# EmgAcq.net
KiCad netlist of a schematic drawn in Altium Designer
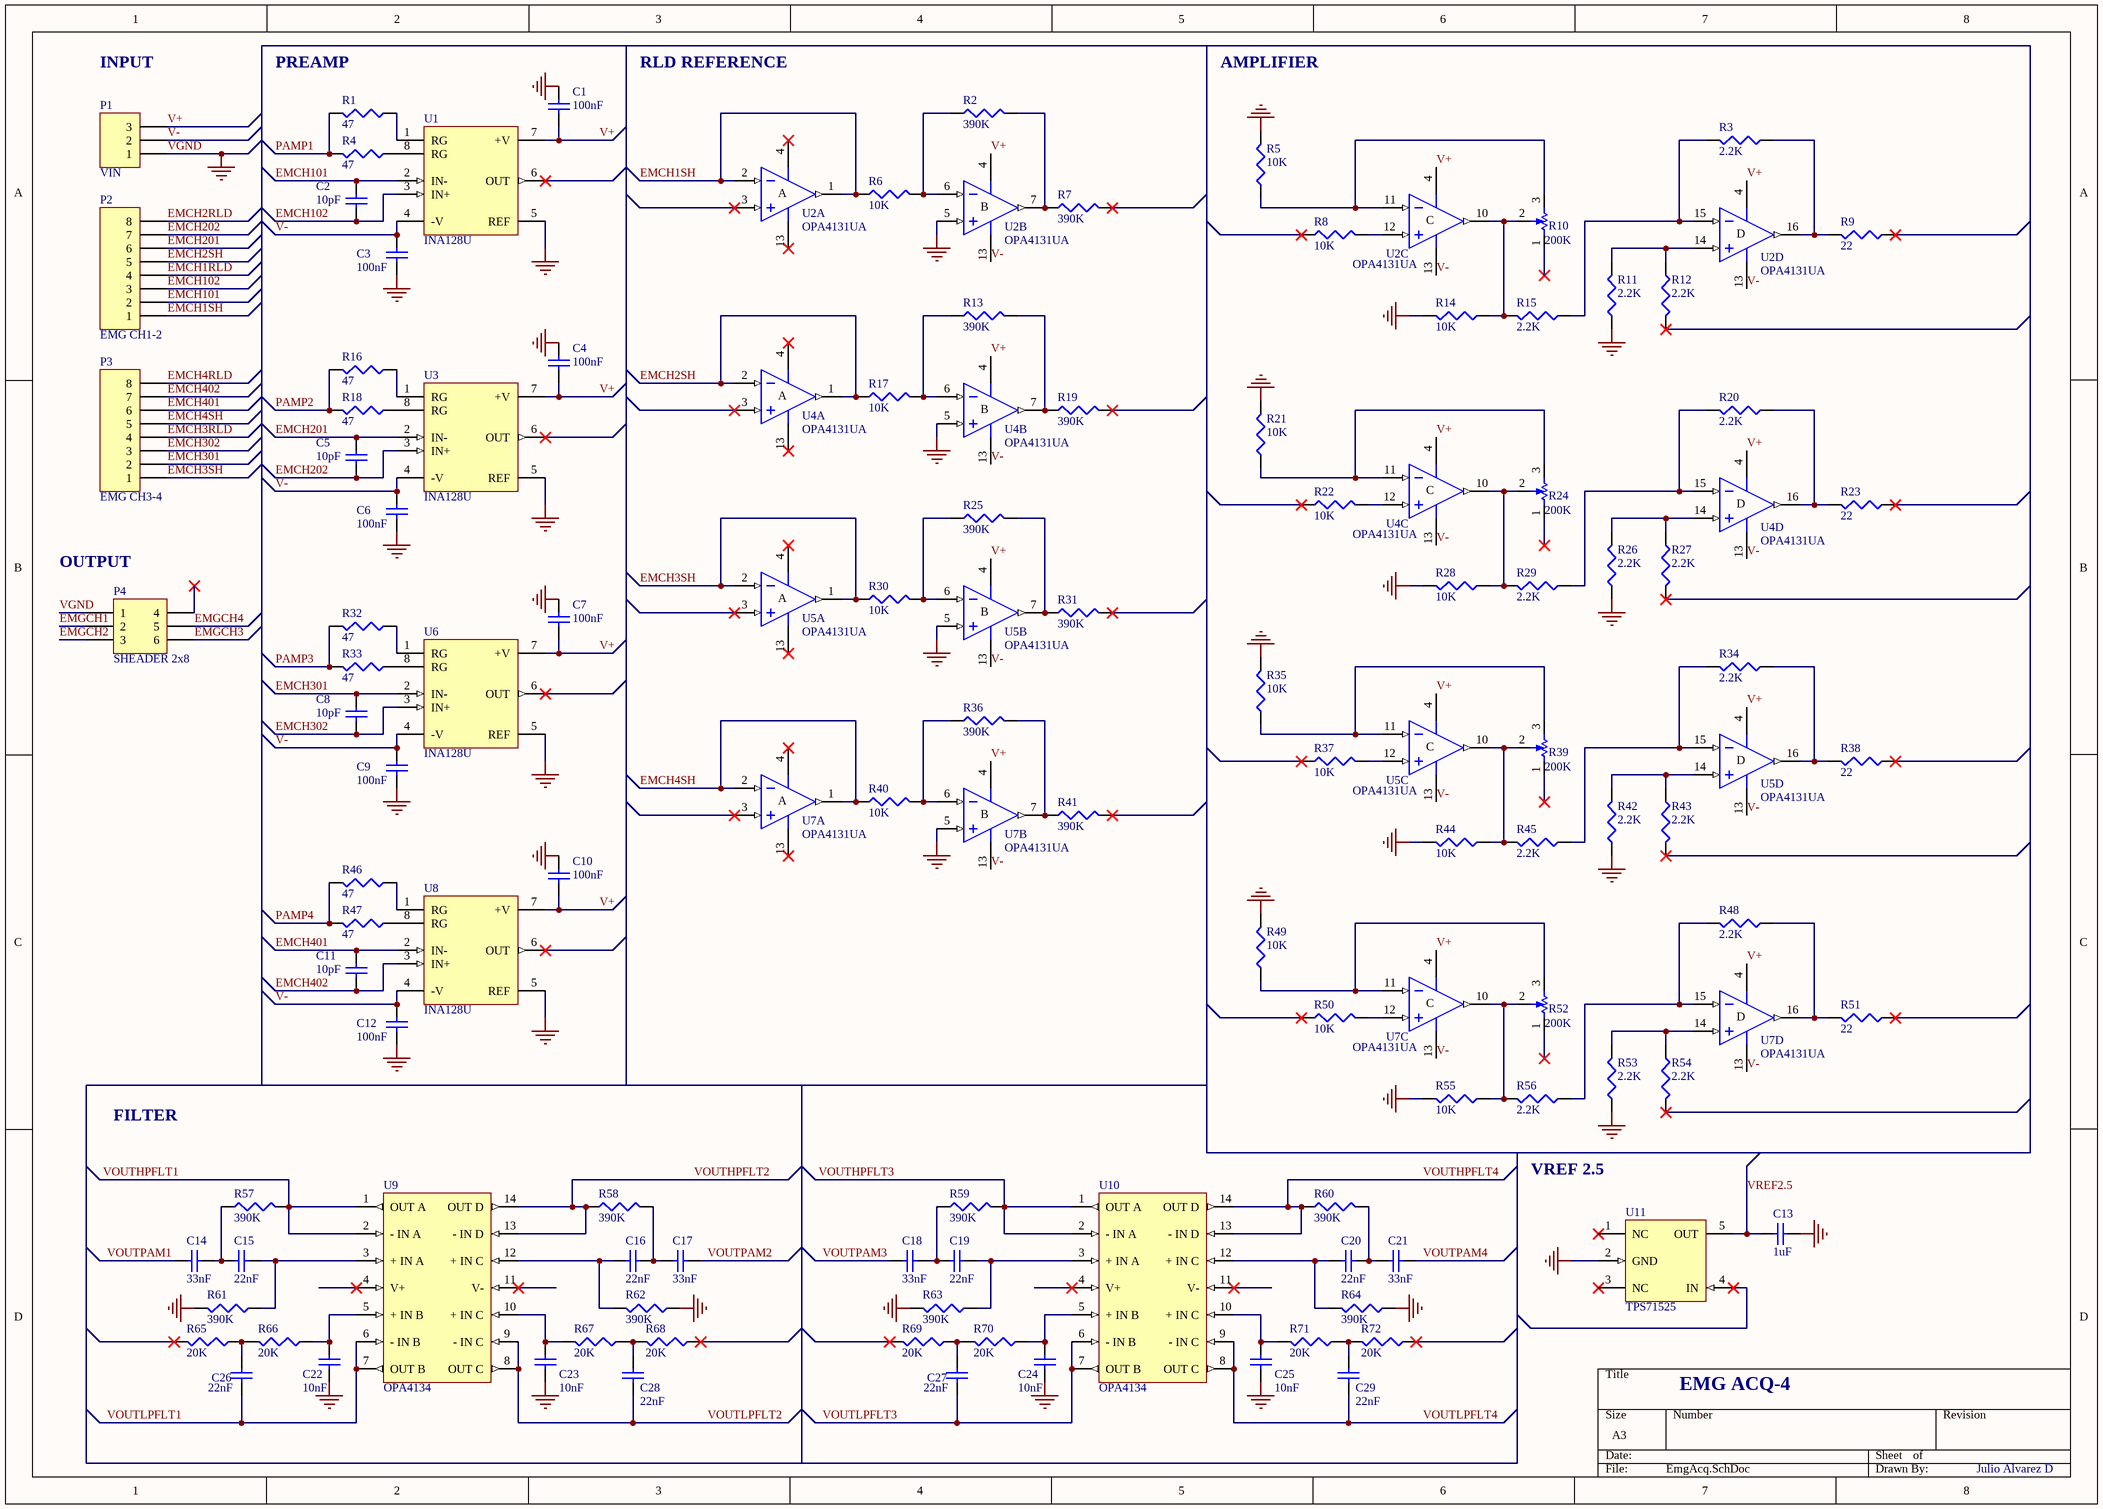
[diagram p0: EmgAcq.SchDoc]

(export (version "E")
  (design (tool "Eeschema 10.0.6"))
  (components
    (comp (ref "C1")
      (value "100nF")
      (footprint "C1206")
      (description "Capacitor (Semiconductor SIM Model)")
      (fields (field (name "Comment") "Cap Semi") (field (name "PUBLISHER") "Altium Limited"))
      (libsource (lib "Miscellaneous Devices") (part "Cap Semi"))
    )
    (comp (ref "C2")
      (value "10pF")
      (footprint "C1206")
      (description "Capacitor (Semiconductor SIM Model)")
      (fields (field (name "Comment") "Cap Semi") (field (name "PUBLISHER") "Altium Limited"))
      (libsource (lib "Miscellaneous Devices") (part "Cap Semi"))
    )
    (comp (ref "C3")
      (value "100nF")
      (footprint "C1206")
      (description "Capacitor (Semiconductor SIM Model)")
      (fields (field (name "Comment") "Cap Semi") (field (name "PUBLISHER") "Altium Limited"))
      (libsource (lib "Miscellaneous Devices") (part "Cap Semi"))
    )
    (comp (ref "C4")
      (value "100nF")
      (footprint "C1206")
      (description "Capacitor (Semiconductor SIM Model)")
      (fields (field (name "Comment") "Cap Semi") (field (name "PUBLISHER") "Altium Limited"))
      (libsource (lib "Miscellaneous Devices") (part "Cap Semi"))
    )
    (comp (ref "C5")
      (value "10pF")
      (footprint "C1206")
      (description "Capacitor (Semiconductor SIM Model)")
      (fields (field (name "Comment") "Cap Semi") (field (name "PUBLISHER") "Altium Limited"))
      (libsource (lib "Miscellaneous Devices") (part "Cap Semi"))
    )
    (comp (ref "C6")
      (value "100nF")
      (footprint "C1206")
      (description "Capacitor (Semiconductor SIM Model)")
      (fields (field (name "Comment") "Cap Semi") (field (name "PUBLISHER") "Altium Limited"))
      (libsource (lib "Miscellaneous Devices") (part "Cap Semi"))
    )
    (comp (ref "C7")
      (value "100nF")
      (footprint "C1206")
      (description "Capacitor (Semiconductor SIM Model)")
      (fields (field (name "Comment") "Cap Semi") (field (name "PUBLISHER") "Altium Limited"))
      (libsource (lib "Miscellaneous Devices") (part "Cap Semi"))
    )
    (comp (ref "C8")
      (value "10pF")
      (footprint "C1206")
      (description "Capacitor (Semiconductor SIM Model)")
      (fields (field (name "Comment") "Cap Semi") (field (name "PUBLISHER") "Altium Limited"))
      (libsource (lib "Miscellaneous Devices") (part "Cap Semi"))
    )
    (comp (ref "C9")
      (value "100nF")
      (footprint "C1206")
      (description "Capacitor (Semiconductor SIM Model)")
      (fields (field (name "Comment") "Cap Semi") (field (name "PUBLISHER") "Altium Limited"))
      (libsource (lib "Miscellaneous Devices") (part "Cap Semi"))
    )
    (comp (ref "C10")
      (value "100nF")
      (footprint "C1206")
      (description "Capacitor (Semiconductor SIM Model)")
      (fields (field (name "Comment") "Cap Semi") (field (name "PUBLISHER") "Altium Limited"))
      (libsource (lib "Miscellaneous Devices") (part "Cap Semi"))
    )
    (comp (ref "C11")
      (value "10pF")
      (footprint "C1206")
      (description "Capacitor (Semiconductor SIM Model)")
      (fields (field (name "Comment") "Cap Semi") (field (name "PUBLISHER") "Altium Limited"))
      (libsource (lib "Miscellaneous Devices") (part "Cap Semi"))
    )
    (comp (ref "C12")
      (value "100nF")
      (footprint "C1206")
      (description "Capacitor (Semiconductor SIM Model)")
      (fields (field (name "Comment") "Cap Semi") (field (name "PUBLISHER") "Altium Limited"))
      (libsource (lib "Miscellaneous Devices") (part "Cap Semi"))
    )
    (comp (ref "C13")
      (value "1uF")
      (footprint "CAPC2012M")
      (description "Capacitor (Semiconductor SIM Model)")
      (fields (field (name "Comment") "Cap Semi") (field (name "PUBLISHER") "Altium Limited"))
      (libsource (lib "Miscellaneous Devices") (part "Cap Semi"))
    )
    (comp (ref "C14")
      (value "33nF")
      (footprint "C1206")
      (description "Capacitor (Semiconductor SIM Model)")
      (fields (field (name "Comment") "Cap Semi") (field (name "PUBLISHER") "Altium Limited"))
      (libsource (lib "Miscellaneous Devices") (part "Cap Semi"))
    )
    (comp (ref "C15")
      (value "22nF")
      (footprint "1608[0603]")
      (description "Capacitor (Semiconductor SIM Model)")
      (fields (field (name "Comment") "Cap Semi") (field (name "PUBLISHER") "Altium Limited"))
      (libsource (lib "Miscellaneous Devices") (part "Cap Semi"))
    )
    (comp (ref "C16")
      (value "22nF")
      (footprint "1608[0603]")
      (description "Capacitor (Semiconductor SIM Model)")
      (fields (field (name "Comment") "Cap Semi") (field (name "PUBLISHER") "Altium Limited"))
      (libsource (lib "Miscellaneous Devices") (part "Cap Semi"))
    )
    (comp (ref "C17")
      (value "33nF")
      (footprint "C1206")
      (description "Capacitor (Semiconductor SIM Model)")
      (fields (field (name "Comment") "Cap Semi") (field (name "PUBLISHER") "Altium Limited"))
      (libsource (lib "Miscellaneous Devices") (part "Cap Semi"))
    )
    (comp (ref "C18")
      (value "33nF")
      (footprint "C1206")
      (description "Capacitor (Semiconductor SIM Model)")
      (fields (field (name "Comment") "Cap Semi") (field (name "PUBLISHER") "Altium Limited"))
      (libsource (lib "Miscellaneous Devices") (part "Cap Semi"))
    )
    (comp (ref "C19")
      (value "22nF")
      (footprint "1608[0603]")
      (description "Capacitor (Semiconductor SIM Model)")
      (fields (field (name "Comment") "Cap Semi") (field (name "PUBLISHER") "Altium Limited"))
      (libsource (lib "Miscellaneous Devices") (part "Cap Semi"))
    )
    (comp (ref "C20")
      (value "22nF")
      (footprint "1608[0603]")
      (description "Capacitor (Semiconductor SIM Model)")
      (fields (field (name "Comment") "Cap Semi") (field (name "PUBLISHER") "Altium Limited"))
      (libsource (lib "Miscellaneous Devices") (part "Cap Semi"))
    )
    (comp (ref "C21")
      (value "33nF")
      (footprint "C1206")
      (description "Capacitor (Semiconductor SIM Model)")
      (fields (field (name "Comment") "Cap Semi") (field (name "PUBLISHER") "Altium Limited"))
      (libsource (lib "Miscellaneous Devices") (part "Cap Semi"))
    )
    (comp (ref "C22")
      (value "10nF")
      (footprint "C1206")
      (description "Capacitor (Semiconductor SIM Model)")
      (fields (field (name "Comment") "Cap Semi") (field (name "PUBLISHER") "Altium Limited"))
      (libsource (lib "Miscellaneous Devices") (part "Cap Semi"))
    )
    (comp (ref "C23")
      (value "10nF")
      (footprint "C1206")
      (description "Capacitor (Semiconductor SIM Model)")
      (fields (field (name "Comment") "Cap Semi") (field (name "PUBLISHER") "Altium Limited"))
      (libsource (lib "Miscellaneous Devices") (part "Cap Semi"))
    )
    (comp (ref "C24")
      (value "10nF")
      (footprint "C1206")
      (description "Capacitor (Semiconductor SIM Model)")
      (fields (field (name "Comment") "Cap Semi") (field (name "PUBLISHER") "Altium Limited"))
      (libsource (lib "Miscellaneous Devices") (part "Cap Semi"))
    )
    (comp (ref "C25")
      (value "10nF")
      (footprint "C1206")
      (description "Capacitor (Semiconductor SIM Model)")
      (fields (field (name "Comment") "Cap Semi") (field (name "PUBLISHER") "Altium Limited"))
      (libsource (lib "Miscellaneous Devices") (part "Cap Semi"))
    )
    (comp (ref "C26")
      (value "22nF")
      (footprint "1608[0603]")
      (description "Capacitor (Semiconductor SIM Model)")
      (fields (field (name "Comment") "Cap Semi") (field (name "PUBLISHER") "Altium Limited"))
      (libsource (lib "Miscellaneous Devices") (part "Cap Semi"))
    )
    (comp (ref "C27")
      (value "22nF")
      (footprint "1608[0603]")
      (description "Capacitor (Semiconductor SIM Model)")
      (fields (field (name "Comment") "Cap Semi") (field (name "PUBLISHER") "Altium Limited"))
      (libsource (lib "Miscellaneous Devices") (part "Cap Semi"))
    )
    (comp (ref "C28")
      (value "22nF")
      (footprint "1608[0603]")
      (description "Capacitor (Semiconductor SIM Model)")
      (fields (field (name "Comment") "Cap Semi") (field (name "PUBLISHER") "Altium Limited"))
      (libsource (lib "Miscellaneous Devices") (part "Cap Semi"))
    )
    (comp (ref "C29")
      (value "22nF")
      (footprint "1608[0603]")
      (description "Capacitor (Semiconductor SIM Model)")
      (fields (field (name "Comment") "Cap Semi") (field (name "PUBLISHER") "Altium Limited"))
      (libsource (lib "Miscellaneous Devices") (part "Cap Semi"))
    )
    (comp (ref "P1")
      (value "VIN")
      (footprint "AZUL5-3")
      (description "Header, 3-Pin")
      (fields (field (name "PUBLISHER") "Altium Limited"))
      (libsource (lib "Miscellaneous Connectors") (part "Header 3"))
    )
    (comp (ref "P2")
      (value "EMG CH1-2")
      (footprint "AZUL5-8")
      (description "Header, 8-Pin")
      (fields (field (name "PUBLISHER") "Altium Limited"))
      (libsource (lib "Miscellaneous Connectors") (part "Header 8"))
    )
    (comp (ref "P3")
      (value "EMG CH3-4")
      (footprint "AZUL5-8")
      (description "Header, 8-Pin")
      (fields (field (name "PUBLISHER") "Altium Limited"))
      (libsource (lib "Miscellaneous Connectors") (part "Header 8"))
    )
    (comp (ref "P4")
      (value "SHEADER 2x8")
      (footprint "SHBH 2x3")
      (description "Shrouded Box Header: 2x8-Pin, 0.100\" (2.54 mm) Male")
      (libsource (lib "LitoLibrary") (part "SB Header 2x3"))
    )
    (comp (ref "R1")
      (value "47")
      (footprint "RESC3225M")
      (description "Resistor")
      (fields (field (name "Comment") "Res3") (field (name "PUBLISHER") "Altium Limited"))
      (libsource (lib "Miscellaneous Devices") (part "Res3"))
    )
    (comp (ref "R2")
      (value "390K")
      (footprint "RESC3225M")
      (description "Resistor")
      (fields (field (name "Comment") "Res3") (field (name "PUBLISHER") "Altium Limited"))
      (libsource (lib "Miscellaneous Devices") (part "Res3"))
    )
    (comp (ref "R3")
      (value "2.2K")
      (footprint "RESC3225M")
      (description "Resistor")
      (fields (field (name "Comment") "Res3") (field (name "PUBLISHER") "Altium Limited"))
      (libsource (lib "Miscellaneous Devices") (part "Res3"))
    )
    (comp (ref "R4")
      (value "47")
      (footprint "RESC3225M")
      (description "Resistor")
      (fields (field (name "Comment") "Res3") (field (name "PUBLISHER") "Altium Limited"))
      (libsource (lib "Miscellaneous Devices") (part "Res3"))
    )
    (comp (ref "R5")
      (value "10K")
      (footprint "RESC3225M")
      (description "Resistor")
      (fields (field (name "Comment") "Res3") (field (name "PUBLISHER") "Altium Limited"))
      (libsource (lib "Miscellaneous Devices") (part "Res3"))
    )
    (comp (ref "R6")
      (value "10K")
      (footprint "RESC3225M")
      (description "Resistor")
      (fields (field (name "Comment") "Res3") (field (name "PUBLISHER") "Altium Limited"))
      (libsource (lib "Miscellaneous Devices") (part "Res3"))
    )
    (comp (ref "R7")
      (value "390K")
      (footprint "RESC3225M")
      (description "Resistor")
      (fields (field (name "Comment") "Res3") (field (name "PUBLISHER") "Altium Limited"))
      (libsource (lib "Miscellaneous Devices") (part "Res3"))
    )
    (comp (ref "R8")
      (value "10K")
      (footprint "RESC3225M")
      (description "Resistor")
      (fields (field (name "Comment") "Res3") (field (name "PUBLISHER") "Altium Limited"))
      (libsource (lib "Miscellaneous Devices") (part "Res3"))
    )
    (comp (ref "R9")
      (value "22")
      (footprint "RESC3225M")
      (description "Resistor")
      (fields (field (name "Comment") "Res3") (field (name "PUBLISHER") "Altium Limited"))
      (libsource (lib "Miscellaneous Devices") (part "Res3"))
    )
    (comp (ref "R10")
      (value "POT3361")
      (footprint "3361P")
      (fields (field (name "ALTIUM_UNNAMED_1") "200K"))
      (libsource (lib "LitoLibrary") (part "POT3361"))
    )
    (comp (ref "R11")
      (value "2.2K")
      (footprint "RESC3225M")
      (description "Resistor")
      (fields (field (name "Comment") "Res3") (field (name "PUBLISHER") "Altium Limited"))
      (libsource (lib "Miscellaneous Devices") (part "Res3"))
    )
    (comp (ref "R12")
      (value "2.2K")
      (footprint "RESC3225M")
      (description "Resistor")
      (fields (field (name "Comment") "Res3") (field (name "PUBLISHER") "Altium Limited"))
      (libsource (lib "Miscellaneous Devices") (part "Res3"))
    )
    (comp (ref "R13")
      (value "390K")
      (footprint "RESC3225M")
      (description "Resistor")
      (fields (field (name "Comment") "Res3") (field (name "PUBLISHER") "Altium Limited"))
      (libsource (lib "Miscellaneous Devices") (part "Res3"))
    )
    (comp (ref "R14")
      (value "10K")
      (footprint "RESC3225M")
      (description "Resistor")
      (fields (field (name "Comment") "Res3") (field (name "PUBLISHER") "Altium Limited"))
      (libsource (lib "Miscellaneous Devices") (part "Res3"))
    )
    (comp (ref "R15")
      (value "2.2K")
      (footprint "RESC3225M")
      (description "Resistor")
      (fields (field (name "Comment") "Res3") (field (name "PUBLISHER") "Altium Limited"))
      (libsource (lib "Miscellaneous Devices") (part "Res3"))
    )
    (comp (ref "R16")
      (value "47")
      (footprint "RESC3225M")
      (description "Resistor")
      (fields (field (name "Comment") "Res3") (field (name "PUBLISHER") "Altium Limited"))
      (libsource (lib "Miscellaneous Devices") (part "Res3"))
    )
    (comp (ref "R17")
      (value "10K")
      (footprint "RESC3225M")
      (description "Resistor")
      (fields (field (name "Comment") "Res3") (field (name "PUBLISHER") "Altium Limited"))
      (libsource (lib "Miscellaneous Devices") (part "Res3"))
    )
    (comp (ref "R18")
      (value "47")
      (footprint "RESC3225M")
      (description "Resistor")
      (fields (field (name "Comment") "Res3") (field (name "PUBLISHER") "Altium Limited"))
      (libsource (lib "Miscellaneous Devices") (part "Res3"))
    )
    (comp (ref "R19")
      (value "390K")
      (footprint "RESC3225M")
      (description "Resistor")
      (fields (field (name "Comment") "Res3") (field (name "PUBLISHER") "Altium Limited"))
      (libsource (lib "Miscellaneous Devices") (part "Res3"))
    )
    (comp (ref "R20")
      (value "2.2K")
      (footprint "RESC3225M")
      (description "Resistor")
      (fields (field (name "Comment") "Res3") (field (name "PUBLISHER") "Altium Limited"))
      (libsource (lib "Miscellaneous Devices") (part "Res3"))
    )
    (comp (ref "R21")
      (value "10K")
      (footprint "RESC3225M")
      (description "Resistor")
      (fields (field (name "Comment") "Res3") (field (name "PUBLISHER") "Altium Limited"))
      (libsource (lib "Miscellaneous Devices") (part "Res3"))
    )
    (comp (ref "R22")
      (value "10K")
      (footprint "RESC3225M")
      (description "Resistor")
      (fields (field (name "Comment") "Res3") (field (name "PUBLISHER") "Altium Limited"))
      (libsource (lib "Miscellaneous Devices") (part "Res3"))
    )
    (comp (ref "R23")
      (value "22")
      (footprint "RESC3225M")
      (description "Resistor")
      (fields (field (name "Comment") "Res3") (field (name "PUBLISHER") "Altium Limited"))
      (libsource (lib "Miscellaneous Devices") (part "Res3"))
    )
    (comp (ref "R24")
      (value "POT3361")
      (footprint "3361P")
      (fields (field (name "ALTIUM_UNNAMED_1") "200K"))
      (libsource (lib "LitoLibrary") (part "POT3361"))
    )
    (comp (ref "R25")
      (value "390K")
      (footprint "RESC3225M")
      (description "Resistor")
      (fields (field (name "Comment") "Res3") (field (name "PUBLISHER") "Altium Limited"))
      (libsource (lib "Miscellaneous Devices") (part "Res3"))
    )
    (comp (ref "R26")
      (value "2.2K")
      (footprint "RESC3225M")
      (description "Resistor")
      (fields (field (name "Comment") "Res3") (field (name "PUBLISHER") "Altium Limited"))
      (libsource (lib "Miscellaneous Devices") (part "Res3"))
    )
    (comp (ref "R27")
      (value "2.2K")
      (footprint "RESC3225M")
      (description "Resistor")
      (fields (field (name "Comment") "Res3") (field (name "PUBLISHER") "Altium Limited"))
      (libsource (lib "Miscellaneous Devices") (part "Res3"))
    )
    (comp (ref "R28")
      (value "10K")
      (footprint "RESC3225M")
      (description "Resistor")
      (fields (field (name "Comment") "Res3") (field (name "PUBLISHER") "Altium Limited"))
      (libsource (lib "Miscellaneous Devices") (part "Res3"))
    )
    (comp (ref "R29")
      (value "2.2K")
      (footprint "RESC3225M")
      (description "Resistor")
      (fields (field (name "Comment") "Res3") (field (name "PUBLISHER") "Altium Limited"))
      (libsource (lib "Miscellaneous Devices") (part "Res3"))
    )
    (comp (ref "R30")
      (value "10K")
      (footprint "RESC3225M")
      (description "Resistor")
      (fields (field (name "Comment") "Res3") (field (name "PUBLISHER") "Altium Limited"))
      (libsource (lib "Miscellaneous Devices") (part "Res3"))
    )
    (comp (ref "R31")
      (value "390K")
      (footprint "RESC3225M")
      (description "Resistor")
      (fields (field (name "Comment") "Res3") (field (name "PUBLISHER") "Altium Limited"))
      (libsource (lib "Miscellaneous Devices") (part "Res3"))
    )
    (comp (ref "R32")
      (value "47")
      (footprint "RESC3225M")
      (description "Resistor")
      (fields (field (name "Comment") "Res3") (field (name "PUBLISHER") "Altium Limited"))
      (libsource (lib "Miscellaneous Devices") (part "Res3"))
    )
    (comp (ref "R33")
      (value "47")
      (footprint "RESC3225M")
      (description "Resistor")
      (fields (field (name "Comment") "Res3") (field (name "PUBLISHER") "Altium Limited"))
      (libsource (lib "Miscellaneous Devices") (part "Res3"))
    )
    (comp (ref "R34")
      (value "2.2K")
      (footprint "RESC3225M")
      (description "Resistor")
      (fields (field (name "Comment") "Res3") (field (name "PUBLISHER") "Altium Limited"))
      (libsource (lib "Miscellaneous Devices") (part "Res3"))
    )
    (comp (ref "R35")
      (value "10K")
      (footprint "RESC3225M")
      (description "Resistor")
      (fields (field (name "Comment") "Res3") (field (name "PUBLISHER") "Altium Limited"))
      (libsource (lib "Miscellaneous Devices") (part "Res3"))
    )
    (comp (ref "R36")
      (value "390K")
      (footprint "RESC3225M")
      (description "Resistor")
      (fields (field (name "Comment") "Res3") (field (name "PUBLISHER") "Altium Limited"))
      (libsource (lib "Miscellaneous Devices") (part "Res3"))
    )
    (comp (ref "R37")
      (value "10K")
      (footprint "RESC3225M")
      (description "Resistor")
      (fields (field (name "Comment") "Res3") (field (name "PUBLISHER") "Altium Limited"))
      (libsource (lib "Miscellaneous Devices") (part "Res3"))
    )
    (comp (ref "R38")
      (value "22")
      (footprint "RESC3225M")
      (description "Resistor")
      (fields (field (name "Comment") "Res3") (field (name "PUBLISHER") "Altium Limited"))
      (libsource (lib "Miscellaneous Devices") (part "Res3"))
    )
    (comp (ref "R39")
      (value "POT3361")
      (footprint "3361P")
      (fields (field (name "ALTIUM_UNNAMED_1") "200K"))
      (libsource (lib "LitoLibrary") (part "POT3361"))
    )
    (comp (ref "R40")
      (value "10K")
      (footprint "RESC3225M")
      (description "Resistor")
      (fields (field (name "Comment") "Res3") (field (name "PUBLISHER") "Altium Limited"))
      (libsource (lib "Miscellaneous Devices") (part "Res3"))
    )
    (comp (ref "R41")
      (value "390K")
      (footprint "RESC3225M")
      (description "Resistor")
      (fields (field (name "Comment") "Res3") (field (name "PUBLISHER") "Altium Limited"))
      (libsource (lib "Miscellaneous Devices") (part "Res3"))
    )
    (comp (ref "R42")
      (value "2.2K")
      (footprint "RESC3225M")
      (description "Resistor")
      (fields (field (name "Comment") "Res3") (field (name "PUBLISHER") "Altium Limited"))
      (libsource (lib "Miscellaneous Devices") (part "Res3"))
    )
    (comp (ref "R43")
      (value "2.2K")
      (footprint "RESC3225M")
      (description "Resistor")
      (fields (field (name "Comment") "Res3") (field (name "PUBLISHER") "Altium Limited"))
      (libsource (lib "Miscellaneous Devices") (part "Res3"))
    )
    (comp (ref "R44")
      (value "10K")
      (footprint "RESC3225M")
      (description "Resistor")
      (fields (field (name "Comment") "Res3") (field (name "PUBLISHER") "Altium Limited"))
      (libsource (lib "Miscellaneous Devices") (part "Res3"))
    )
    (comp (ref "R45")
      (value "2.2K")
      (footprint "RESC3225M")
      (description "Resistor")
      (fields (field (name "Comment") "Res3") (field (name "PUBLISHER") "Altium Limited"))
      (libsource (lib "Miscellaneous Devices") (part "Res3"))
    )
    (comp (ref "R46")
      (value "47")
      (footprint "RESC3225M")
      (description "Resistor")
      (fields (field (name "Comment") "Res3") (field (name "PUBLISHER") "Altium Limited"))
      (libsource (lib "Miscellaneous Devices") (part "Res3"))
    )
    (comp (ref "R47")
      (value "47")
      (footprint "RESC3225M")
      (description "Resistor")
      (fields (field (name "Comment") "Res3") (field (name "PUBLISHER") "Altium Limited"))
      (libsource (lib "Miscellaneous Devices") (part "Res3"))
    )
    (comp (ref "R48")
      (value "2.2K")
      (footprint "RESC3225M")
      (description "Resistor")
      (fields (field (name "Comment") "Res3") (field (name "PUBLISHER") "Altium Limited"))
      (libsource (lib "Miscellaneous Devices") (part "Res3"))
    )
    (comp (ref "R49")
      (value "10K")
      (footprint "RESC3225M")
      (description "Resistor")
      (fields (field (name "Comment") "Res3") (field (name "PUBLISHER") "Altium Limited"))
      (libsource (lib "Miscellaneous Devices") (part "Res3"))
    )
    (comp (ref "R50")
      (value "10K")
      (footprint "RESC3225M")
      (description "Resistor")
      (fields (field (name "Comment") "Res3") (field (name "PUBLISHER") "Altium Limited"))
      (libsource (lib "Miscellaneous Devices") (part "Res3"))
    )
    (comp (ref "R51")
      (value "22")
      (footprint "RESC3225M")
      (description "Resistor")
      (fields (field (name "Comment") "Res3") (field (name "PUBLISHER") "Altium Limited"))
      (libsource (lib "Miscellaneous Devices") (part "Res3"))
    )
    (comp (ref "R52")
      (value "POT3361")
      (footprint "3361P")
      (fields (field (name "ALTIUM_UNNAMED_1") "200K"))
      (libsource (lib "LitoLibrary") (part "POT3361"))
    )
    (comp (ref "R53")
      (value "2.2K")
      (footprint "RESC3225M")
      (description "Resistor")
      (fields (field (name "Comment") "Res3") (field (name "PUBLISHER") "Altium Limited"))
      (libsource (lib "Miscellaneous Devices") (part "Res3"))
    )
    (comp (ref "R54")
      (value "2.2K")
      (footprint "RESC3225M")
      (description "Resistor")
      (fields (field (name "Comment") "Res3") (field (name "PUBLISHER") "Altium Limited"))
      (libsource (lib "Miscellaneous Devices") (part "Res3"))
    )
    (comp (ref "R55")
      (value "10K")
      (footprint "RESC3225M")
      (description "Resistor")
      (fields (field (name "Comment") "Res3") (field (name "PUBLISHER") "Altium Limited"))
      (libsource (lib "Miscellaneous Devices") (part "Res3"))
    )
    (comp (ref "R56")
      (value "2.2K")
      (footprint "RESC3225M")
      (description "Resistor")
      (fields (field (name "Comment") "Res3") (field (name "PUBLISHER") "Altium Limited"))
      (libsource (lib "Miscellaneous Devices") (part "Res3"))
    )
    (comp (ref "R57")
      (value "390K")
      (footprint "RESC3225M")
      (description "Resistor")
      (fields (field (name "Comment") "Res3") (field (name "PUBLISHER") "Altium Limited"))
      (libsource (lib "Miscellaneous Devices") (part "Res3"))
    )
    (comp (ref "R58")
      (value "390K")
      (footprint "RESC3225M")
      (description "Resistor")
      (fields (field (name "Comment") "Res3") (field (name "PUBLISHER") "Altium Limited"))
      (libsource (lib "Miscellaneous Devices") (part "Res3"))
    )
    (comp (ref "R59")
      (value "390K")
      (footprint "RESC3225M")
      (description "Resistor")
      (fields (field (name "Comment") "Res3") (field (name "PUBLISHER") "Altium Limited"))
      (libsource (lib "Miscellaneous Devices") (part "Res3"))
    )
    (comp (ref "R60")
      (value "390K")
      (footprint "RESC3225M")
      (description "Resistor")
      (fields (field (name "Comment") "Res3") (field (name "PUBLISHER") "Altium Limited"))
      (libsource (lib "Miscellaneous Devices") (part "Res3"))
    )
    (comp (ref "R61")
      (value "390K")
      (footprint "RESC3225M")
      (description "Resistor")
      (fields (field (name "Comment") "Res3") (field (name "PUBLISHER") "Altium Limited"))
      (libsource (lib "Miscellaneous Devices") (part "Res3"))
    )
    (comp (ref "R62")
      (value "390K")
      (footprint "RESC3225M")
      (description "Resistor")
      (fields (field (name "Comment") "Res3") (field (name "PUBLISHER") "Altium Limited"))
      (libsource (lib "Miscellaneous Devices") (part "Res3"))
    )
    (comp (ref "R63")
      (value "390K")
      (footprint "RESC3225M")
      (description "Resistor")
      (fields (field (name "Comment") "Res3") (field (name "PUBLISHER") "Altium Limited"))
      (libsource (lib "Miscellaneous Devices") (part "Res3"))
    )
    (comp (ref "R64")
      (value "390K")
      (footprint "RESC3225M")
      (description "Resistor")
      (fields (field (name "Comment") "Res3") (field (name "PUBLISHER") "Altium Limited"))
      (libsource (lib "Miscellaneous Devices") (part "Res3"))
    )
    (comp (ref "R65")
      (value "20K")
      (footprint "RESC3225M")
      (description "Resistor")
      (fields (field (name "Comment") "Res3") (field (name "PUBLISHER") "Altium Limited"))
      (libsource (lib "Miscellaneous Devices") (part "Res3"))
    )
    (comp (ref "R66")
      (value "20K")
      (footprint "RESC3225M")
      (description "Resistor")
      (fields (field (name "Comment") "Res3") (field (name "PUBLISHER") "Altium Limited"))
      (libsource (lib "Miscellaneous Devices") (part "Res3"))
    )
    (comp (ref "R67")
      (value "20K")
      (footprint "RESC3225M")
      (description "Resistor")
      (fields (field (name "Comment") "Res3") (field (name "PUBLISHER") "Altium Limited"))
      (libsource (lib "Miscellaneous Devices") (part "Res3"))
    )
    (comp (ref "R68")
      (value "20K")
      (footprint "RESC3225M")
      (description "Resistor")
      (fields (field (name "Comment") "Res3") (field (name "PUBLISHER") "Altium Limited"))
      (libsource (lib "Miscellaneous Devices") (part "Res3"))
    )
    (comp (ref "R69")
      (value "20K")
      (footprint "RESC3225M")
      (description "Resistor")
      (fields (field (name "Comment") "Res3") (field (name "PUBLISHER") "Altium Limited"))
      (libsource (lib "Miscellaneous Devices") (part "Res3"))
    )
    (comp (ref "R70")
      (value "20K")
      (footprint "RESC3225M")
      (description "Resistor")
      (fields (field (name "Comment") "Res3") (field (name "PUBLISHER") "Altium Limited"))
      (libsource (lib "Miscellaneous Devices") (part "Res3"))
    )
    (comp (ref "R71")
      (value "20K")
      (footprint "RESC3225M")
      (description "Resistor")
      (fields (field (name "Comment") "Res3") (field (name "PUBLISHER") "Altium Limited"))
      (libsource (lib "Miscellaneous Devices") (part "Res3"))
    )
    (comp (ref "R72")
      (value "20K")
      (footprint "RESC3225M")
      (description "Resistor")
      (fields (field (name "Comment") "Res3") (field (name "PUBLISHER") "Altium Limited"))
      (libsource (lib "Miscellaneous Devices") (part "Res3"))
    )
    (comp (ref "U1")
      (value "INA128U")
      (footprint "182H_N")
      (description "Precision, Low-Power Instrumentation Amplifiers")
      (fields (field (name "PUBLISHER") "Altium Limited"))
      (libsource (lib "BB Instrumentation Amplifier") (part "INA128U"))
    )
    (comp (ref "U2")
      (value "OPA4131UA")
      (footprint "211F_N")
      (description "General Purpose FET-Input Operational Amplifiers")
      (fields (field (name "PUBLISHER") "Altium Limited"))
      (libsource (lib "BB Operational Amplifier") (part "OPA4131UA"))
    )
    (comp (ref "U3")
      (value "INA128U")
      (footprint "182H_N")
      (description "Precision, Low-Power Instrumentation Amplifiers")
      (fields (field (name "PUBLISHER") "Altium Limited"))
      (libsource (lib "BB Instrumentation Amplifier") (part "INA128U"))
    )
    (comp (ref "U4")
      (value "OPA4131UA")
      (footprint "211F_N")
      (description "General Purpose FET-Input Operational Amplifiers")
      (fields (field (name "PUBLISHER") "Altium Limited"))
      (libsource (lib "BB Operational Amplifier") (part "OPA4131UA"))
    )
    (comp (ref "U5")
      (value "OPA4131UA")
      (footprint "211F_N")
      (description "General Purpose FET-Input Operational Amplifiers")
      (fields (field (name "PUBLISHER") "Altium Limited"))
      (libsource (lib "BB Operational Amplifier") (part "OPA4131UA"))
    )
    (comp (ref "U6")
      (value "INA128U")
      (footprint "182H_N")
      (description "Precision, Low-Power Instrumentation Amplifiers")
      (fields (field (name "PUBLISHER") "Altium Limited"))
      (libsource (lib "BB Instrumentation Amplifier") (part "INA128U"))
    )
    (comp (ref "U7")
      (value "OPA4131UA")
      (footprint "211F_N")
      (description "General Purpose FET-Input Operational Amplifiers")
      (fields (field (name "PUBLISHER") "Altium Limited"))
      (libsource (lib "BB Operational Amplifier") (part "OPA4131UA"))
    )
    (comp (ref "U8")
      (value "INA128U")
      (footprint "182H_N")
      (description "Precision, Low-Power Instrumentation Amplifiers")
      (fields (field (name "PUBLISHER") "Altium Limited"))
      (libsource (lib "BB Instrumentation Amplifier") (part "INA128U"))
    )
    (comp (ref "U9")
      (value "OPA4134")
      (footprint "SOIC127P600-14M")
      (libsource (lib "LitoLibrary") (part "OPA4134"))
    )
    (comp (ref "U10")
      (value "OPA4134")
      (footprint "SOIC127P600-14M")
      (libsource (lib "LitoLibrary") (part "OPA4134"))
    )
    (comp (ref "U11")
      (value "TPS71525")
      (footprint "SOT353-5L")
      (libsource (lib "LitoLibrary") (part "TPS71525"))
    )
  )
  (nets
    (net (code "1") (name "/EMCH1RLD") (class "Default")
      (node (ref "P2") (pin "4") (pinfunction "4_4") (pintype "passive"))
    )
    (net (code "2") (name "/EMCH1SH") (class "Default")
      (node (ref "P2") (pin "1") (pinfunction "1_1") (pintype "passive"))
      (node (ref "R6") (pin "1") (pinfunction "1_1") (pintype "passive"))
      (node (ref "U2") (pin "1") (pinfunction "OUT_1") (pintype "output"))
      (node (ref "U2") (pin "2") (pinfunction "IN-_2") (pintype "input"))
    )
    (net (code "3") (name "/EMCH2RLD") (class "Default")
      (node (ref "P2") (pin "8") (pinfunction "8_8") (pintype "passive"))
    )
    (net (code "4") (name "/EMCH2SH") (class "Default")
      (node (ref "P2") (pin "5") (pinfunction "5_5") (pintype "passive"))
      (node (ref "R17") (pin "1") (pinfunction "1_1") (pintype "passive"))
      (node (ref "U4") (pin "1") (pinfunction "OUT_1") (pintype "output"))
      (node (ref "U4") (pin "2") (pinfunction "IN-_2") (pintype "input"))
    )
    (net (code "5") (name "/EMCH3RLD") (class "Default")
      (node (ref "P3") (pin "4") (pinfunction "4_4") (pintype "passive"))
    )
    (net (code "6") (name "/EMCH3SH") (class "Default")
      (node (ref "P3") (pin "1") (pinfunction "1_1") (pintype "passive"))
      (node (ref "R30") (pin "1") (pinfunction "1_1") (pintype "passive"))
      (node (ref "U5") (pin "1") (pinfunction "OUT_1") (pintype "output"))
      (node (ref "U5") (pin "2") (pinfunction "IN-_2") (pintype "input"))
    )
    (net (code "7") (name "/EMCH4RLD") (class "Default")
      (node (ref "P3") (pin "8") (pinfunction "8_8") (pintype "passive"))
    )
    (net (code "8") (name "/EMCH4SH") (class "Default")
      (node (ref "P3") (pin "5") (pinfunction "5_5") (pintype "passive"))
      (node (ref "R40") (pin "1") (pinfunction "1_1") (pintype "passive"))
      (node (ref "U7") (pin "1") (pinfunction "OUT_1") (pintype "output"))
      (node (ref "U7") (pin "2") (pinfunction "IN-_2") (pintype "input"))
    )
    (net (code "9") (name "/EMCH101") (class "Default")
      (node (ref "C2") (pin "2") (pinfunction "2_2") (pintype "passive"))
      (node (ref "P2") (pin "2") (pinfunction "2_2") (pintype "passive"))
      (node (ref "U1") (pin "2") (pinfunction "IN-_2") (pintype "input"))
    )
    (net (code "10") (name "/EMCH102") (class "Default")
      (node (ref "C2") (pin "1") (pinfunction "1_1") (pintype "passive"))
      (node (ref "P2") (pin "3") (pinfunction "3_3") (pintype "passive"))
      (node (ref "U1") (pin "3") (pinfunction "IN+_3") (pintype "input"))
    )
    (net (code "11") (name "/EMCH201") (class "Default")
      (node (ref "C5") (pin "2") (pinfunction "2_2") (pintype "passive"))
      (node (ref "P2") (pin "6") (pinfunction "6_6") (pintype "passive"))
      (node (ref "U3") (pin "2") (pinfunction "IN-_2") (pintype "input"))
    )
    (net (code "12") (name "/EMCH202") (class "Default")
      (node (ref "C5") (pin "1") (pinfunction "1_1") (pintype "passive"))
      (node (ref "P2") (pin "7") (pinfunction "7_7") (pintype "passive"))
      (node (ref "U3") (pin "3") (pinfunction "IN+_3") (pintype "input"))
    )
    (net (code "13") (name "/EMCH301") (class "Default")
      (node (ref "C8") (pin "2") (pinfunction "2_2") (pintype "passive"))
      (node (ref "P3") (pin "2") (pinfunction "2_2") (pintype "passive"))
      (node (ref "U6") (pin "2") (pinfunction "IN-_2") (pintype "input"))
    )
    (net (code "14") (name "/EMCH302") (class "Default")
      (node (ref "C8") (pin "1") (pinfunction "1_1") (pintype "passive"))
      (node (ref "P3") (pin "3") (pinfunction "3_3") (pintype "passive"))
      (node (ref "U6") (pin "3") (pinfunction "IN+_3") (pintype "input"))
    )
    (net (code "15") (name "/EMCH401") (class "Default")
      (node (ref "C11") (pin "2") (pinfunction "2_2") (pintype "passive"))
      (node (ref "P3") (pin "6") (pinfunction "6_6") (pintype "passive"))
      (node (ref "U8") (pin "2") (pinfunction "IN-_2") (pintype "input"))
    )
    (net (code "16") (name "/EMCH402") (class "Default")
      (node (ref "C11") (pin "1") (pinfunction "1_1") (pintype "passive"))
      (node (ref "P3") (pin "7") (pinfunction "7_7") (pintype "passive"))
      (node (ref "U8") (pin "3") (pinfunction "IN+_3") (pintype "input"))
    )
    (net (code "17") (name "/EMGCH1") (class "Default")
      (node (ref "P4") (pin "2") (pinfunction "2_2") (pintype "passive"))
    )
    (net (code "18") (name "/EMGCH2") (class "Default")
      (node (ref "P4") (pin "3") (pinfunction "3_3") (pintype "passive"))
    )
    (net (code "19") (name "/EMGCH3") (class "Default")
      (node (ref "P4") (pin "6") (pinfunction "6_6") (pintype "passive"))
    )
    (net (code "20") (name "/EMGCH4") (class "Default")
      (node (ref "P4") (pin "5") (pinfunction "5_5") (pintype "passive"))
    )
    (net (code "21") (name "/PAMP1") (class "Default")
      (node (ref "R1") (pin "2") (pinfunction "2_2") (pintype "passive"))
      (node (ref "R4") (pin "2") (pinfunction "2_2") (pintype "passive"))
    )
    (net (code "22") (name "/PAMP2") (class "Default")
      (node (ref "R16") (pin "2") (pinfunction "2_2") (pintype "passive"))
      (node (ref "R18") (pin "2") (pinfunction "2_2") (pintype "passive"))
    )
    (net (code "23") (name "/PAMP3") (class "Default")
      (node (ref "R32") (pin "2") (pinfunction "2_2") (pintype "passive"))
      (node (ref "R33") (pin "2") (pinfunction "2_2") (pintype "passive"))
    )
    (net (code "24") (name "/PAMP4") (class "Default")
      (node (ref "R46") (pin "2") (pinfunction "2_2") (pintype "passive"))
      (node (ref "R47") (pin "2") (pinfunction "2_2") (pintype "passive"))
    )
    (net (code "25") (name "/V+") (class "Default")
      (node (ref "C1") (pin "1") (pinfunction "1_1") (pintype "passive"))
      (node (ref "C10") (pin "1") (pinfunction "1_1") (pintype "passive"))
      (node (ref "C4") (pin "1") (pinfunction "1_1") (pintype "passive"))
      (node (ref "C7") (pin "1") (pinfunction "1_1") (pintype "passive"))
      (node (ref "P1") (pin "3") (pinfunction "3_3") (pintype "passive"))
      (node (ref "U1") (pin "7") (pinfunction "+V_7") (pintype "power_in"))
      (node (ref "U2") (pin "4") (pinfunction "V+_4") (pintype "power_in"))
      (node (ref "U3") (pin "7") (pinfunction "+V_7") (pintype "power_in"))
      (node (ref "U4") (pin "4") (pinfunction "V+_4") (pintype "power_in"))
      (node (ref "U5") (pin "4") (pinfunction "V+_4") (pintype "power_in"))
      (node (ref "U6") (pin "7") (pinfunction "+V_7") (pintype "power_in"))
      (node (ref "U7") (pin "4") (pinfunction "V+_4") (pintype "power_in"))
      (node (ref "U8") (pin "7") (pinfunction "+V_7") (pintype "power_in"))
    )
    (net (code "26") (name "/V-") (class "Default")
      (node (ref "C12") (pin "2") (pinfunction "2_2") (pintype "passive"))
      (node (ref "C3") (pin "2") (pinfunction "2_2") (pintype "passive"))
      (node (ref "C6") (pin "2") (pinfunction "2_2") (pintype "passive"))
      (node (ref "C9") (pin "2") (pinfunction "2_2") (pintype "passive"))
      (node (ref "P1") (pin "2") (pinfunction "2_2") (pintype "passive"))
      (node (ref "U1") (pin "4") (pinfunction "-V_4") (pintype "power_in"))
      (node (ref "U2") (pin "13") (pinfunction "V-_13") (pintype "power_in"))
      (node (ref "U3") (pin "4") (pinfunction "-V_4") (pintype "power_in"))
      (node (ref "U4") (pin "13") (pinfunction "V-_13") (pintype "power_in"))
      (node (ref "U5") (pin "13") (pinfunction "V-_13") (pintype "power_in"))
      (node (ref "U6") (pin "4") (pinfunction "-V_4") (pintype "power_in"))
      (node (ref "U7") (pin "13") (pinfunction "V-_13") (pintype "power_in"))
      (node (ref "U8") (pin "4") (pinfunction "-V_4") (pintype "power_in"))
    )
    (net (code "27") (name "/VOUTHPFLT1") (class "Default")
      (node (ref "R57") (pin "2") (pinfunction "2_2") (pintype "passive"))
      (node (ref "U9") (pin "1") (pinfunction "OUT_A_1") (pintype "output"))
      (node (ref "U9") (pin "2") (pinfunction "-_IN_A_2") (pintype "input"))
    )
    (net (code "28") (name "/VOUTHPFLT2") (class "Default")
      (node (ref "R58") (pin "2") (pinfunction "2_2") (pintype "passive"))
      (node (ref "U9") (pin "13") (pinfunction "-_IN_D_13") (pintype "input"))
      (node (ref "U9") (pin "14") (pinfunction "OUT_D_14") (pintype "output"))
    )
    (net (code "29") (name "/VOUTHPFLT3") (class "Default")
      (node (ref "R59") (pin "2") (pinfunction "2_2") (pintype "passive"))
      (node (ref "U10") (pin "1") (pinfunction "OUT_A_1") (pintype "output"))
      (node (ref "U10") (pin "2") (pinfunction "-_IN_A_2") (pintype "input"))
    )
    (net (code "30") (name "/VOUTHPFLT4") (class "Default")
      (node (ref "R60") (pin "2") (pinfunction "2_2") (pintype "passive"))
      (node (ref "U10") (pin "13") (pinfunction "-_IN_D_13") (pintype "input"))
      (node (ref "U10") (pin "14") (pinfunction "OUT_D_14") (pintype "output"))
    )
    (net (code "31") (name "/VOUTLPFLT1") (class "Default")
      (node (ref "C26") (pin "1") (pinfunction "1_1") (pintype "passive"))
      (node (ref "U9") (pin "6") (pinfunction "-_IN_B_6") (pintype "input"))
      (node (ref "U9") (pin "7") (pinfunction "OUT_B_7") (pintype "output"))
    )
    (net (code "32") (name "/VOUTLPFLT2") (class "Default")
      (node (ref "C28") (pin "1") (pinfunction "1_1") (pintype "passive"))
      (node (ref "U9") (pin "8") (pinfunction "OUT_C_8") (pintype "output"))
      (node (ref "U9") (pin "9") (pinfunction "-_IN_C_9") (pintype "input"))
    )
    (net (code "33") (name "/VOUTLPFLT3") (class "Default")
      (node (ref "C27") (pin "1") (pinfunction "1_1") (pintype "passive"))
      (node (ref "U10") (pin "6") (pinfunction "-_IN_B_6") (pintype "input"))
      (node (ref "U10") (pin "7") (pinfunction "OUT_B_7") (pintype "output"))
    )
    (net (code "34") (name "/VOUTLPFLT4") (class "Default")
      (node (ref "C29") (pin "1") (pinfunction "1_1") (pintype "passive"))
      (node (ref "U10") (pin "8") (pinfunction "OUT_C_8") (pintype "output"))
      (node (ref "U10") (pin "9") (pinfunction "-_IN_C_9") (pintype "input"))
    )
    (net (code "35") (name "/VOUTPAM1") (class "Default")
      (node (ref "C14") (pin "2") (pinfunction "2_2") (pintype "passive"))
    )
    (net (code "36") (name "/VOUTPAM2") (class "Default")
      (node (ref "C17") (pin "2") (pinfunction "2_2") (pintype "passive"))
    )
    (net (code "37") (name "/VOUTPAM3") (class "Default")
      (node (ref "C18") (pin "2") (pinfunction "2_2") (pintype "passive"))
    )
    (net (code "38") (name "/VOUTPAM4") (class "Default")
      (node (ref "C21") (pin "2") (pinfunction "2_2") (pintype "passive"))
    )
    (net (code "39") (name "/VREF2.5") (class "Default")
      (node (ref "C13") (pin "1") (pinfunction "1_1") (pintype "passive"))
      (node (ref "U11") (pin "5") (pinfunction "OUT_5") (pintype "passive"))
    )
    (net (code "40") (name "GND") (class "Default")
      (node (ref "C1") (pin "2") (pinfunction "2_2") (pintype "passive"))
      (node (ref "C10") (pin "2") (pinfunction "2_2") (pintype "passive"))
      (node (ref "C12") (pin "1") (pinfunction "1_1") (pintype "passive"))
      (node (ref "C13") (pin "2") (pinfunction "2_2") (pintype "passive"))
      (node (ref "C22") (pin "1") (pinfunction "1_1") (pintype "passive"))
      (node (ref "C23") (pin "1") (pinfunction "1_1") (pintype "passive"))
      (node (ref "C24") (pin "1") (pinfunction "1_1") (pintype "passive"))
      (node (ref "C25") (pin "1") (pinfunction "1_1") (pintype "passive"))
      (node (ref "C3") (pin "1") (pinfunction "1_1") (pintype "passive"))
      (node (ref "C4") (pin "2") (pinfunction "2_2") (pintype "passive"))
      (node (ref "C6") (pin "1") (pinfunction "1_1") (pintype "passive"))
      (node (ref "C7") (pin "2") (pinfunction "2_2") (pintype "passive"))
      (node (ref "C9") (pin "1") (pinfunction "1_1") (pintype "passive"))
      (node (ref "P1") (pin "1") (pinfunction "1_1") (pintype "passive"))
      (node (ref "P4") (pin "1") (pinfunction "1_1") (pintype "passive"))
      (node (ref "R11") (pin "2") (pinfunction "2_2") (pintype "passive"))
      (node (ref "R14") (pin "1") (pinfunction "1_1") (pintype "passive"))
      (node (ref "R21") (pin "1") (pinfunction "1_1") (pintype "passive"))
      (node (ref "R26") (pin "2") (pinfunction "2_2") (pintype "passive"))
      (node (ref "R28") (pin "1") (pinfunction "1_1") (pintype "passive"))
      (node (ref "R35") (pin "1") (pinfunction "1_1") (pintype "passive"))
      (node (ref "R42") (pin "2") (pinfunction "2_2") (pintype "passive"))
      (node (ref "R44") (pin "1") (pinfunction "1_1") (pintype "passive"))
      (node (ref "R49") (pin "1") (pinfunction "1_1") (pintype "passive"))
      (node (ref "R5") (pin "1") (pinfunction "1_1") (pintype "passive"))
      (node (ref "R53") (pin "2") (pinfunction "2_2") (pintype "passive"))
      (node (ref "R55") (pin "1") (pinfunction "1_1") (pintype "passive"))
      (node (ref "R61") (pin "2") (pinfunction "2_2") (pintype "passive"))
      (node (ref "R62") (pin "2") (pinfunction "2_2") (pintype "passive"))
      (node (ref "R63") (pin "2") (pinfunction "2_2") (pintype "passive"))
      (node (ref "R64") (pin "2") (pinfunction "2_2") (pintype "passive"))
      (node (ref "U1") (pin "5") (pinfunction "REF_5") (pintype "passive"))
      (node (ref "U11") (pin "2") (pinfunction "GND_2") (pintype "input"))
      (node (ref "U2") (pin "5") (pinfunction "IN+_5") (pintype "input"))
      (node (ref "U3") (pin "5") (pinfunction "REF_5") (pintype "passive"))
      (node (ref "U4") (pin "5") (pinfunction "IN+_5") (pintype "input"))
      (node (ref "U5") (pin "5") (pinfunction "IN+_5") (pintype "input"))
      (node (ref "U6") (pin "5") (pinfunction "REF_5") (pintype "passive"))
      (node (ref "U7") (pin "5") (pinfunction "IN+_5") (pintype "input"))
      (node (ref "U8") (pin "5") (pinfunction "REF_5") (pintype "passive"))
    )
    (net (code "41") (name "Net-(C14-Pad1)") (class "Default")
      (node (ref "C14") (pin "1") (pinfunction "1_1") (pintype "passive"))
      (node (ref "C15") (pin "2") (pinfunction "2_2") (pintype "passive"))
      (node (ref "R57") (pin "1") (pinfunction "1_1") (pintype "passive"))
    )
    (net (code "42") (name "Net-(C16-Pad1)") (class "Default")
      (node (ref "C16") (pin "1") (pinfunction "1_1") (pintype "passive"))
      (node (ref "R62") (pin "1") (pinfunction "1_1") (pintype "passive"))
      (node (ref "U9") (pin "12") (pinfunction "+_IN_C_12") (pintype "input"))
    )
    (net (code "43") (name "Net-(C16-Pad2)") (class "Default")
      (node (ref "C16") (pin "2") (pinfunction "2_2") (pintype "passive"))
      (node (ref "C17") (pin "1") (pinfunction "1_1") (pintype "passive"))
      (node (ref "R58") (pin "1") (pinfunction "1_1") (pintype "passive"))
    )
    (net (code "44") (name "Net-(C18-Pad1)") (class "Default")
      (node (ref "C18") (pin "1") (pinfunction "1_1") (pintype "passive"))
      (node (ref "C19") (pin "2") (pinfunction "2_2") (pintype "passive"))
      (node (ref "R59") (pin "1") (pinfunction "1_1") (pintype "passive"))
    )
    (net (code "45") (name "Net-(C20-Pad1)") (class "Default")
      (node (ref "C20") (pin "1") (pinfunction "1_1") (pintype "passive"))
      (node (ref "R64") (pin "1") (pinfunction "1_1") (pintype "passive"))
      (node (ref "U10") (pin "12") (pinfunction "+_IN_C_12") (pintype "input"))
    )
    (net (code "46") (name "Net-(C20-Pad2)") (class "Default")
      (node (ref "C20") (pin "2") (pinfunction "2_2") (pintype "passive"))
      (node (ref "C21") (pin "1") (pinfunction "1_1") (pintype "passive"))
      (node (ref "R60") (pin "1") (pinfunction "1_1") (pintype "passive"))
    )
    (net (code "47") (name "Net-(C23-Pad2)") (class "Default")
      (node (ref "C23") (pin "2") (pinfunction "2_2") (pintype "passive"))
      (node (ref "R67") (pin "1") (pinfunction "1_1") (pintype "passive"))
      (node (ref "U9") (pin "10") (pinfunction "+_IN_C_10") (pintype "input"))
    )
    (net (code "48") (name "Net-(C25-Pad2)") (class "Default")
      (node (ref "C25") (pin "2") (pinfunction "2_2") (pintype "passive"))
      (node (ref "R71") (pin "1") (pinfunction "1_1") (pintype "passive"))
      (node (ref "U10") (pin "10") (pinfunction "+_IN_C_10") (pintype "input"))
    )
    (net (code "49") (name "Net-(C26-Pad2)") (class "Default")
      (node (ref "C26") (pin "2") (pinfunction "2_2") (pintype "passive"))
      (node (ref "R65") (pin "1") (pinfunction "1_1") (pintype "passive"))
      (node (ref "R66") (pin "2") (pinfunction "2_2") (pintype "passive"))
    )
    (net (code "50") (name "Net-(C27-Pad2)") (class "Default")
      (node (ref "C27") (pin "2") (pinfunction "2_2") (pintype "passive"))
      (node (ref "R69") (pin "1") (pinfunction "1_1") (pintype "passive"))
      (node (ref "R70") (pin "2") (pinfunction "2_2") (pintype "passive"))
    )
    (net (code "51") (name "Net-(C28-Pad2)") (class "Default")
      (node (ref "C28") (pin "2") (pinfunction "2_2") (pintype "passive"))
      (node (ref "R67") (pin "2") (pinfunction "2_2") (pintype "passive"))
      (node (ref "R68") (pin "1") (pinfunction "1_1") (pintype "passive"))
    )
    (net (code "52") (name "Net-(C29-Pad2)") (class "Default")
      (node (ref "C29") (pin "2") (pinfunction "2_2") (pintype "passive"))
      (node (ref "R71") (pin "2") (pinfunction "2_2") (pintype "passive"))
      (node (ref "R72") (pin "1") (pinfunction "1_1") (pintype "passive"))
    )
    (net (code "53") (name "Net-(R1-Pad1)") (class "Default")
      (node (ref "R1") (pin "1") (pinfunction "1_1") (pintype "passive"))
      (node (ref "U1") (pin "1") (pinfunction "RG_1") (pintype "passive"))
    )
    (net (code "54") (name "Net-(R4-Pad1)") (class "Default")
      (node (ref "R4") (pin "1") (pinfunction "1_1") (pintype "passive"))
      (node (ref "U1") (pin "8") (pinfunction "RG_8") (pintype "passive"))
    )
    (net (code "55") (name "Net-(R16-Pad1)") (class "Default")
      (node (ref "R16") (pin "1") (pinfunction "1_1") (pintype "passive"))
      (node (ref "U3") (pin "1") (pinfunction "RG_1") (pintype "passive"))
    )
    (net (code "56") (name "Net-(R18-Pad1)") (class "Default")
      (node (ref "R18") (pin "1") (pinfunction "1_1") (pintype "passive"))
      (node (ref "U3") (pin "8") (pinfunction "RG_8") (pintype "passive"))
    )
    (net (code "57") (name "Net-(R32-Pad1)") (class "Default")
      (node (ref "R32") (pin "1") (pinfunction "1_1") (pintype "passive"))
      (node (ref "U6") (pin "1") (pinfunction "RG_1") (pintype "passive"))
    )
    (net (code "58") (name "Net-(R33-Pad1)") (class "Default")
      (node (ref "R33") (pin "1") (pinfunction "1_1") (pintype "passive"))
      (node (ref "U6") (pin "8") (pinfunction "RG_8") (pintype "passive"))
    )
    (net (code "59") (name "Net-(R46-Pad1)") (class "Default")
      (node (ref "R46") (pin "1") (pinfunction "1_1") (pintype "passive"))
      (node (ref "U8") (pin "1") (pinfunction "RG_1") (pintype "passive"))
    )
    (net (code "60") (name "Net-(R47-Pad1)") (class "Default")
      (node (ref "R47") (pin "1") (pinfunction "1_1") (pintype "passive"))
      (node (ref "U8") (pin "8") (pinfunction "RG_8") (pintype "passive"))
    )
    (net (code "61") (name "Net-(U2B-IN-)") (class "Default")
      (node (ref "R2") (pin "1") (pinfunction "1_1") (pintype "passive"))
      (node (ref "R6") (pin "2") (pinfunction "2_2") (pintype "passive"))
      (node (ref "U2") (pin "6") (pinfunction "IN-_6") (pintype "input"))
    )
    (net (code "62") (name "Net-(U2B-OUT)") (class "Default")
      (node (ref "R2") (pin "2") (pinfunction "2_2") (pintype "passive"))
      (node (ref "R7") (pin "1") (pinfunction "1_1") (pintype "passive"))
      (node (ref "U2") (pin "7") (pinfunction "OUT_7") (pintype "output"))
    )
    (net (code "63") (name "Net-(U2C-IN+)") (class "Default")
      (node (ref "R8") (pin "1") (pinfunction "1_1") (pintype "passive"))
      (node (ref "U2") (pin "12") (pinfunction "IN+_12") (pintype "input"))
    )
    (net (code "64") (name "Net-(U2C-IN-)") (class "Default")
      (node (ref "R10") (pin "3") (pinfunction "3_3") (pintype "passive"))
      (node (ref "R5") (pin "2") (pinfunction "2_2") (pintype "passive"))
      (node (ref "U2") (pin "11") (pinfunction "IN-_11") (pintype "input"))
    )
    (net (code "65") (name "Net-(U2C-OUT)") (class "Default")
      (node (ref "R10") (pin "2") (pinfunction "2_2") (pintype "passive"))
      (node (ref "R14") (pin "2") (pinfunction "2_2") (pintype "passive"))
      (node (ref "R15") (pin "1") (pinfunction "1_1") (pintype "passive"))
      (node (ref "U2") (pin "10") (pinfunction "OUT_10") (pintype "output"))
    )
    (net (code "66") (name "Net-(U2D-IN+)") (class "Default")
      (node (ref "R11") (pin "1") (pinfunction "1_1") (pintype "passive"))
      (node (ref "R12") (pin "2") (pinfunction "2_2") (pintype "passive"))
      (node (ref "U2") (pin "14") (pinfunction "IN+_14") (pintype "input"))
    )
    (net (code "67") (name "Net-(U2D-IN-)") (class "Default")
      (node (ref "R15") (pin "2") (pinfunction "2_2") (pintype "passive"))
      (node (ref "R3") (pin "1") (pinfunction "1_1") (pintype "passive"))
      (node (ref "U2") (pin "15") (pinfunction "IN-_15") (pintype "input"))
    )
    (net (code "68") (name "Net-(U2D-OUT)") (class "Default")
      (node (ref "R3") (pin "2") (pinfunction "2_2") (pintype "passive"))
      (node (ref "R9") (pin "1") (pinfunction "1_1") (pintype "passive"))
      (node (ref "U2") (pin "16") (pinfunction "OUT_16") (pintype "output"))
    )
    (net (code "69") (name "Net-(U4B-IN-)") (class "Default")
      (node (ref "R13") (pin "1") (pinfunction "1_1") (pintype "passive"))
      (node (ref "R17") (pin "2") (pinfunction "2_2") (pintype "passive"))
      (node (ref "U4") (pin "6") (pinfunction "IN-_6") (pintype "input"))
    )
    (net (code "70") (name "Net-(U4B-OUT)") (class "Default")
      (node (ref "R13") (pin "2") (pinfunction "2_2") (pintype "passive"))
      (node (ref "R19") (pin "1") (pinfunction "1_1") (pintype "passive"))
      (node (ref "U4") (pin "7") (pinfunction "OUT_7") (pintype "output"))
    )
    (net (code "71") (name "Net-(U4C-IN+)") (class "Default")
      (node (ref "R22") (pin "1") (pinfunction "1_1") (pintype "passive"))
      (node (ref "U4") (pin "12") (pinfunction "IN+_12") (pintype "input"))
    )
    (net (code "72") (name "Net-(U4C-IN-)") (class "Default")
      (node (ref "R21") (pin "2") (pinfunction "2_2") (pintype "passive"))
      (node (ref "R24") (pin "3") (pinfunction "3_3") (pintype "passive"))
      (node (ref "U4") (pin "11") (pinfunction "IN-_11") (pintype "input"))
    )
    (net (code "73") (name "Net-(U4C-OUT)") (class "Default")
      (node (ref "R24") (pin "2") (pinfunction "2_2") (pintype "passive"))
      (node (ref "R28") (pin "2") (pinfunction "2_2") (pintype "passive"))
      (node (ref "R29") (pin "1") (pinfunction "1_1") (pintype "passive"))
      (node (ref "U4") (pin "10") (pinfunction "OUT_10") (pintype "output"))
    )
    (net (code "74") (name "Net-(U4D-IN+)") (class "Default")
      (node (ref "R26") (pin "1") (pinfunction "1_1") (pintype "passive"))
      (node (ref "R27") (pin "2") (pinfunction "2_2") (pintype "passive"))
      (node (ref "U4") (pin "14") (pinfunction "IN+_14") (pintype "input"))
    )
    (net (code "75") (name "Net-(U4D-IN-)") (class "Default")
      (node (ref "R20") (pin "1") (pinfunction "1_1") (pintype "passive"))
      (node (ref "R29") (pin "2") (pinfunction "2_2") (pintype "passive"))
      (node (ref "U4") (pin "15") (pinfunction "IN-_15") (pintype "input"))
    )
    (net (code "76") (name "Net-(U4D-OUT)") (class "Default")
      (node (ref "R20") (pin "2") (pinfunction "2_2") (pintype "passive"))
      (node (ref "R23") (pin "1") (pinfunction "1_1") (pintype "passive"))
      (node (ref "U4") (pin "16") (pinfunction "OUT_16") (pintype "output"))
    )
    (net (code "77") (name "Net-(U5B-IN-)") (class "Default")
      (node (ref "R25") (pin "1") (pinfunction "1_1") (pintype "passive"))
      (node (ref "R30") (pin "2") (pinfunction "2_2") (pintype "passive"))
      (node (ref "U5") (pin "6") (pinfunction "IN-_6") (pintype "input"))
    )
    (net (code "78") (name "Net-(U5B-OUT)") (class "Default")
      (node (ref "R25") (pin "2") (pinfunction "2_2") (pintype "passive"))
      (node (ref "R31") (pin "1") (pinfunction "1_1") (pintype "passive"))
      (node (ref "U5") (pin "7") (pinfunction "OUT_7") (pintype "output"))
    )
    (net (code "79") (name "Net-(U5C-IN+)") (class "Default")
      (node (ref "R37") (pin "1") (pinfunction "1_1") (pintype "passive"))
      (node (ref "U5") (pin "12") (pinfunction "IN+_12") (pintype "input"))
    )
    (net (code "80") (name "Net-(U5C-IN-)") (class "Default")
      (node (ref "R35") (pin "2") (pinfunction "2_2") (pintype "passive"))
      (node (ref "R39") (pin "3") (pinfunction "3_3") (pintype "passive"))
      (node (ref "U5") (pin "11") (pinfunction "IN-_11") (pintype "input"))
    )
    (net (code "81") (name "Net-(U5C-OUT)") (class "Default")
      (node (ref "R39") (pin "2") (pinfunction "2_2") (pintype "passive"))
      (node (ref "R44") (pin "2") (pinfunction "2_2") (pintype "passive"))
      (node (ref "R45") (pin "1") (pinfunction "1_1") (pintype "passive"))
      (node (ref "U5") (pin "10") (pinfunction "OUT_10") (pintype "output"))
    )
    (net (code "82") (name "Net-(U5D-IN+)") (class "Default")
      (node (ref "R42") (pin "1") (pinfunction "1_1") (pintype "passive"))
      (node (ref "R43") (pin "2") (pinfunction "2_2") (pintype "passive"))
      (node (ref "U5") (pin "14") (pinfunction "IN+_14") (pintype "input"))
    )
    (net (code "83") (name "Net-(U5D-IN-)") (class "Default")
      (node (ref "R34") (pin "1") (pinfunction "1_1") (pintype "passive"))
      (node (ref "R45") (pin "2") (pinfunction "2_2") (pintype "passive"))
      (node (ref "U5") (pin "15") (pinfunction "IN-_15") (pintype "input"))
    )
    (net (code "84") (name "Net-(U5D-OUT)") (class "Default")
      (node (ref "R34") (pin "2") (pinfunction "2_2") (pintype "passive"))
      (node (ref "R38") (pin "1") (pinfunction "1_1") (pintype "passive"))
      (node (ref "U5") (pin "16") (pinfunction "OUT_16") (pintype "output"))
    )
    (net (code "85") (name "Net-(U7B-IN-)") (class "Default")
      (node (ref "R36") (pin "1") (pinfunction "1_1") (pintype "passive"))
      (node (ref "R40") (pin "2") (pinfunction "2_2") (pintype "passive"))
      (node (ref "U7") (pin "6") (pinfunction "IN-_6") (pintype "input"))
    )
    (net (code "86") (name "Net-(U7B-OUT)") (class "Default")
      (node (ref "R36") (pin "2") (pinfunction "2_2") (pintype "passive"))
      (node (ref "R41") (pin "1") (pinfunction "1_1") (pintype "passive"))
      (node (ref "U7") (pin "7") (pinfunction "OUT_7") (pintype "output"))
    )
    (net (code "87") (name "Net-(U7C-IN+)") (class "Default")
      (node (ref "R50") (pin "1") (pinfunction "1_1") (pintype "passive"))
      (node (ref "U7") (pin "12") (pinfunction "IN+_12") (pintype "input"))
    )
    (net (code "88") (name "Net-(U7C-IN-)") (class "Default")
      (node (ref "R49") (pin "2") (pinfunction "2_2") (pintype "passive"))
      (node (ref "R52") (pin "3") (pinfunction "3_3") (pintype "passive"))
      (node (ref "U7") (pin "11") (pinfunction "IN-_11") (pintype "input"))
    )
    (net (code "89") (name "Net-(U7C-OUT)") (class "Default")
      (node (ref "R52") (pin "2") (pinfunction "2_2") (pintype "passive"))
      (node (ref "R55") (pin "2") (pinfunction "2_2") (pintype "passive"))
      (node (ref "R56") (pin "1") (pinfunction "1_1") (pintype "passive"))
      (node (ref "U7") (pin "10") (pinfunction "OUT_10") (pintype "output"))
    )
    (net (code "90") (name "Net-(U7D-IN+)") (class "Default")
      (node (ref "R53") (pin "1") (pinfunction "1_1") (pintype "passive"))
      (node (ref "R54") (pin "2") (pinfunction "2_2") (pintype "passive"))
      (node (ref "U7") (pin "14") (pinfunction "IN+_14") (pintype "input"))
    )
    (net (code "91") (name "Net-(U7D-IN-)") (class "Default")
      (node (ref "R48") (pin "1") (pinfunction "1_1") (pintype "passive"))
      (node (ref "R56") (pin "2") (pinfunction "2_2") (pintype "passive"))
      (node (ref "U7") (pin "15") (pinfunction "IN-_15") (pintype "input"))
    )
    (net (code "92") (name "Net-(U7D-OUT)") (class "Default")
      (node (ref "R48") (pin "2") (pinfunction "2_2") (pintype "passive"))
      (node (ref "R51") (pin "1") (pinfunction "1_1") (pintype "passive"))
      (node (ref "U7") (pin "16") (pinfunction "OUT_16") (pintype "output"))
    )
    (net (code "93") (name "Net-(U9-+_IN_A)") (class "Default")
      (node (ref "C15") (pin "1") (pinfunction "1_1") (pintype "passive"))
      (node (ref "R61") (pin "1") (pinfunction "1_1") (pintype "passive"))
      (node (ref "U9") (pin "3") (pinfunction "+_IN_A_3") (pintype "input"))
    )
    (net (code "94") (name "Net-(U9-+_IN_B)") (class "Default")
      (node (ref "C22") (pin "2") (pinfunction "2_2") (pintype "passive"))
      (node (ref "R66") (pin "1") (pinfunction "1_1") (pintype "passive"))
      (node (ref "U9") (pin "5") (pinfunction "+_IN_B_5") (pintype "input"))
    )
    (net (code "95") (name "Net-(U10-+_IN_A)") (class "Default")
      (node (ref "C19") (pin "1") (pinfunction "1_1") (pintype "passive"))
      (node (ref "R63") (pin "1") (pinfunction "1_1") (pintype "passive"))
      (node (ref "U10") (pin "3") (pinfunction "+_IN_A_3") (pintype "input"))
    )
    (net (code "96") (name "Net-(U10-+_IN_B)") (class "Default")
      (node (ref "C24") (pin "2") (pinfunction "2_2") (pintype "passive"))
      (node (ref "R70") (pin "1") (pinfunction "1_1") (pintype "passive"))
      (node (ref "U10") (pin "5") (pinfunction "+_IN_B_5") (pintype "input"))
    )
    (net (code "97") (name "unconnected-(P4-Pad4)") (class "Default")
      (node (ref "P4") (pin "4") (pinfunction "4_4") (pintype "passive+no_connect"))
    )
    (net (code "98") (name "unconnected-(R7-Pad2)") (class "Default")
      (node (ref "R7") (pin "2") (pinfunction "2_2") (pintype "passive+no_connect"))
    )
    (net (code "99") (name "unconnected-(R8-Pad2)") (class "Default")
      (node (ref "R8") (pin "2") (pinfunction "2_2") (pintype "passive+no_connect"))
    )
    (net (code "100") (name "unconnected-(R9-Pad2)") (class "Default")
      (node (ref "R9") (pin "2") (pinfunction "2_2") (pintype "passive+no_connect"))
    )
    (net (code "101") (name "unconnected-(R10-Pad1)") (class "Default")
      (node (ref "R10") (pin "1") (pinfunction "1_1") (pintype "passive+no_connect"))
    )
    (net (code "102") (name "unconnected-(R12-Pad1)") (class "Default")
      (node (ref "R12") (pin "1") (pinfunction "1_1") (pintype "passive+no_connect"))
    )
    (net (code "103") (name "unconnected-(R19-Pad2)") (class "Default")
      (node (ref "R19") (pin "2") (pinfunction "2_2") (pintype "passive+no_connect"))
    )
    (net (code "104") (name "unconnected-(R22-Pad2)") (class "Default")
      (node (ref "R22") (pin "2") (pinfunction "2_2") (pintype "passive+no_connect"))
    )
    (net (code "105") (name "unconnected-(R23-Pad2)") (class "Default")
      (node (ref "R23") (pin "2") (pinfunction "2_2") (pintype "passive+no_connect"))
    )
    (net (code "106") (name "unconnected-(R24-Pad1)") (class "Default")
      (node (ref "R24") (pin "1") (pinfunction "1_1") (pintype "passive+no_connect"))
    )
    (net (code "107") (name "unconnected-(R27-Pad1)") (class "Default")
      (node (ref "R27") (pin "1") (pinfunction "1_1") (pintype "passive+no_connect"))
    )
    (net (code "108") (name "unconnected-(R31-Pad2)") (class "Default")
      (node (ref "R31") (pin "2") (pinfunction "2_2") (pintype "passive+no_connect"))
    )
    (net (code "109") (name "unconnected-(R37-Pad2)") (class "Default")
      (node (ref "R37") (pin "2") (pinfunction "2_2") (pintype "passive+no_connect"))
    )
    (net (code "110") (name "unconnected-(R38-Pad2)") (class "Default")
      (node (ref "R38") (pin "2") (pinfunction "2_2") (pintype "passive+no_connect"))
    )
    (net (code "111") (name "unconnected-(R39-Pad1)") (class "Default")
      (node (ref "R39") (pin "1") (pinfunction "1_1") (pintype "passive+no_connect"))
    )
    (net (code "112") (name "unconnected-(R41-Pad2)") (class "Default")
      (node (ref "R41") (pin "2") (pinfunction "2_2") (pintype "passive+no_connect"))
    )
    (net (code "113") (name "unconnected-(R43-Pad1)") (class "Default")
      (node (ref "R43") (pin "1") (pinfunction "1_1") (pintype "passive+no_connect"))
    )
    (net (code "114") (name "unconnected-(R50-Pad2)") (class "Default")
      (node (ref "R50") (pin "2") (pinfunction "2_2") (pintype "passive+no_connect"))
    )
    (net (code "115") (name "unconnected-(R51-Pad2)") (class "Default")
      (node (ref "R51") (pin "2") (pinfunction "2_2") (pintype "passive+no_connect"))
    )
    (net (code "116") (name "unconnected-(R52-Pad1)") (class "Default")
      (node (ref "R52") (pin "1") (pinfunction "1_1") (pintype "passive+no_connect"))
    )
    (net (code "117") (name "unconnected-(R54-Pad1)") (class "Default")
      (node (ref "R54") (pin "1") (pinfunction "1_1") (pintype "passive+no_connect"))
    )
    (net (code "118") (name "unconnected-(R65-Pad2)") (class "Default")
      (node (ref "R65") (pin "2") (pinfunction "2_2") (pintype "passive+no_connect"))
    )
    (net (code "119") (name "unconnected-(R68-Pad2)") (class "Default")
      (node (ref "R68") (pin "2") (pinfunction "2_2") (pintype "passive+no_connect"))
    )
    (net (code "120") (name "unconnected-(R69-Pad2)") (class "Default")
      (node (ref "R69") (pin "2") (pinfunction "2_2") (pintype "passive+no_connect"))
    )
    (net (code "121") (name "unconnected-(R72-Pad2)") (class "Default")
      (node (ref "R72") (pin "2") (pinfunction "2_2") (pintype "passive+no_connect"))
    )
    (net (code "122") (name "unconnected-(U1-OUT-Pad6)") (class "Default")
      (node (ref "U1") (pin "6") (pinfunction "OUT_6") (pintype "output+no_connect"))
    )
    (net (code "123") (name "unconnected-(U2A-IN+-Pad3)") (class "Default")
      (node (ref "U2") (pin "3") (pinfunction "IN+_3") (pintype "input+no_connect"))
    )
    (net (code "124") (name "unconnected-(U2A-V+-Pad4)") (class "Default")
      (node (ref "U2") (pin "4") (pinfunction "V+_4") (pintype "power_in+no_connect"))
    )
    (net (code "125") (name "unconnected-(U2A-V--Pad13)") (class "Default")
      (node (ref "U2") (pin "13") (pinfunction "V-_13") (pintype "power_in+no_connect"))
    )
    (net (code "126") (name "unconnected-(U3-OUT-Pad6)") (class "Default")
      (node (ref "U3") (pin "6") (pinfunction "OUT_6") (pintype "output+no_connect"))
    )
    (net (code "127") (name "unconnected-(U4A-IN+-Pad3)") (class "Default")
      (node (ref "U4") (pin "3") (pinfunction "IN+_3") (pintype "input+no_connect"))
    )
    (net (code "128") (name "unconnected-(U4A-V+-Pad4)") (class "Default")
      (node (ref "U4") (pin "4") (pinfunction "V+_4") (pintype "power_in+no_connect"))
    )
    (net (code "129") (name "unconnected-(U4A-V--Pad13)") (class "Default")
      (node (ref "U4") (pin "13") (pinfunction "V-_13") (pintype "power_in+no_connect"))
    )
    (net (code "130") (name "unconnected-(U5A-IN+-Pad3)") (class "Default")
      (node (ref "U5") (pin "3") (pinfunction "IN+_3") (pintype "input+no_connect"))
    )
    (net (code "131") (name "unconnected-(U5A-V+-Pad4)") (class "Default")
      (node (ref "U5") (pin "4") (pinfunction "V+_4") (pintype "power_in+no_connect"))
    )
    (net (code "132") (name "unconnected-(U5A-V--Pad13)") (class "Default")
      (node (ref "U5") (pin "13") (pinfunction "V-_13") (pintype "power_in+no_connect"))
    )
    (net (code "133") (name "unconnected-(U6-OUT-Pad6)") (class "Default")
      (node (ref "U6") (pin "6") (pinfunction "OUT_6") (pintype "output+no_connect"))
    )
    (net (code "134") (name "unconnected-(U7A-IN+-Pad3)") (class "Default")
      (node (ref "U7") (pin "3") (pinfunction "IN+_3") (pintype "input+no_connect"))
    )
    (net (code "135") (name "unconnected-(U7A-V+-Pad4)") (class "Default")
      (node (ref "U7") (pin "4") (pinfunction "V+_4") (pintype "power_in+no_connect"))
    )
    (net (code "136") (name "unconnected-(U7A-V--Pad13)") (class "Default")
      (node (ref "U7") (pin "13") (pinfunction "V-_13") (pintype "power_in+no_connect"))
    )
    (net (code "137") (name "unconnected-(U8-OUT-Pad6)") (class "Default")
      (node (ref "U8") (pin "6") (pinfunction "OUT_6") (pintype "output+no_connect"))
    )
    (net (code "138") (name "unconnected-(U9-V+-Pad4)") (class "Default")
      (node (ref "U9") (pin "4") (pinfunction "V+_4") (pintype "input+no_connect"))
    )
    (net (code "139") (name "unconnected-(U9-V--Pad11)") (class "Default")
      (node (ref "U9") (pin "11") (pinfunction "V-_11") (pintype "input+no_connect"))
    )
    (net (code "140") (name "unconnected-(U10-V+-Pad4)") (class "Default")
      (node (ref "U10") (pin "4") (pinfunction "V+_4") (pintype "input+no_connect"))
    )
    (net (code "141") (name "unconnected-(U10-V--Pad11)") (class "Default")
      (node (ref "U10") (pin "11") (pinfunction "V-_11") (pintype "input+no_connect"))
    )
    (net (code "142") (name "unconnected-(U11-IN-Pad4)") (class "Default")
      (node (ref "U11") (pin "4") (pinfunction "IN_4") (pintype "input+no_connect"))
    )
    (net (code "143") (name "unconnected-(U11-NC-Pad1)") (class "Default")
      (node (ref "U11") (pin "1") (pinfunction "NC_1") (pintype "passive+no_connect"))
    )
    (net (code "144") (name "unconnected-(U11-NC-Pad3)") (class "Default")
      (node (ref "U11") (pin "3") (pinfunction "NC_3") (pintype "passive+no_connect"))
    )
  )
)
